# big_shield.net
KiCad netlist of a schematic drawn in EAGLE
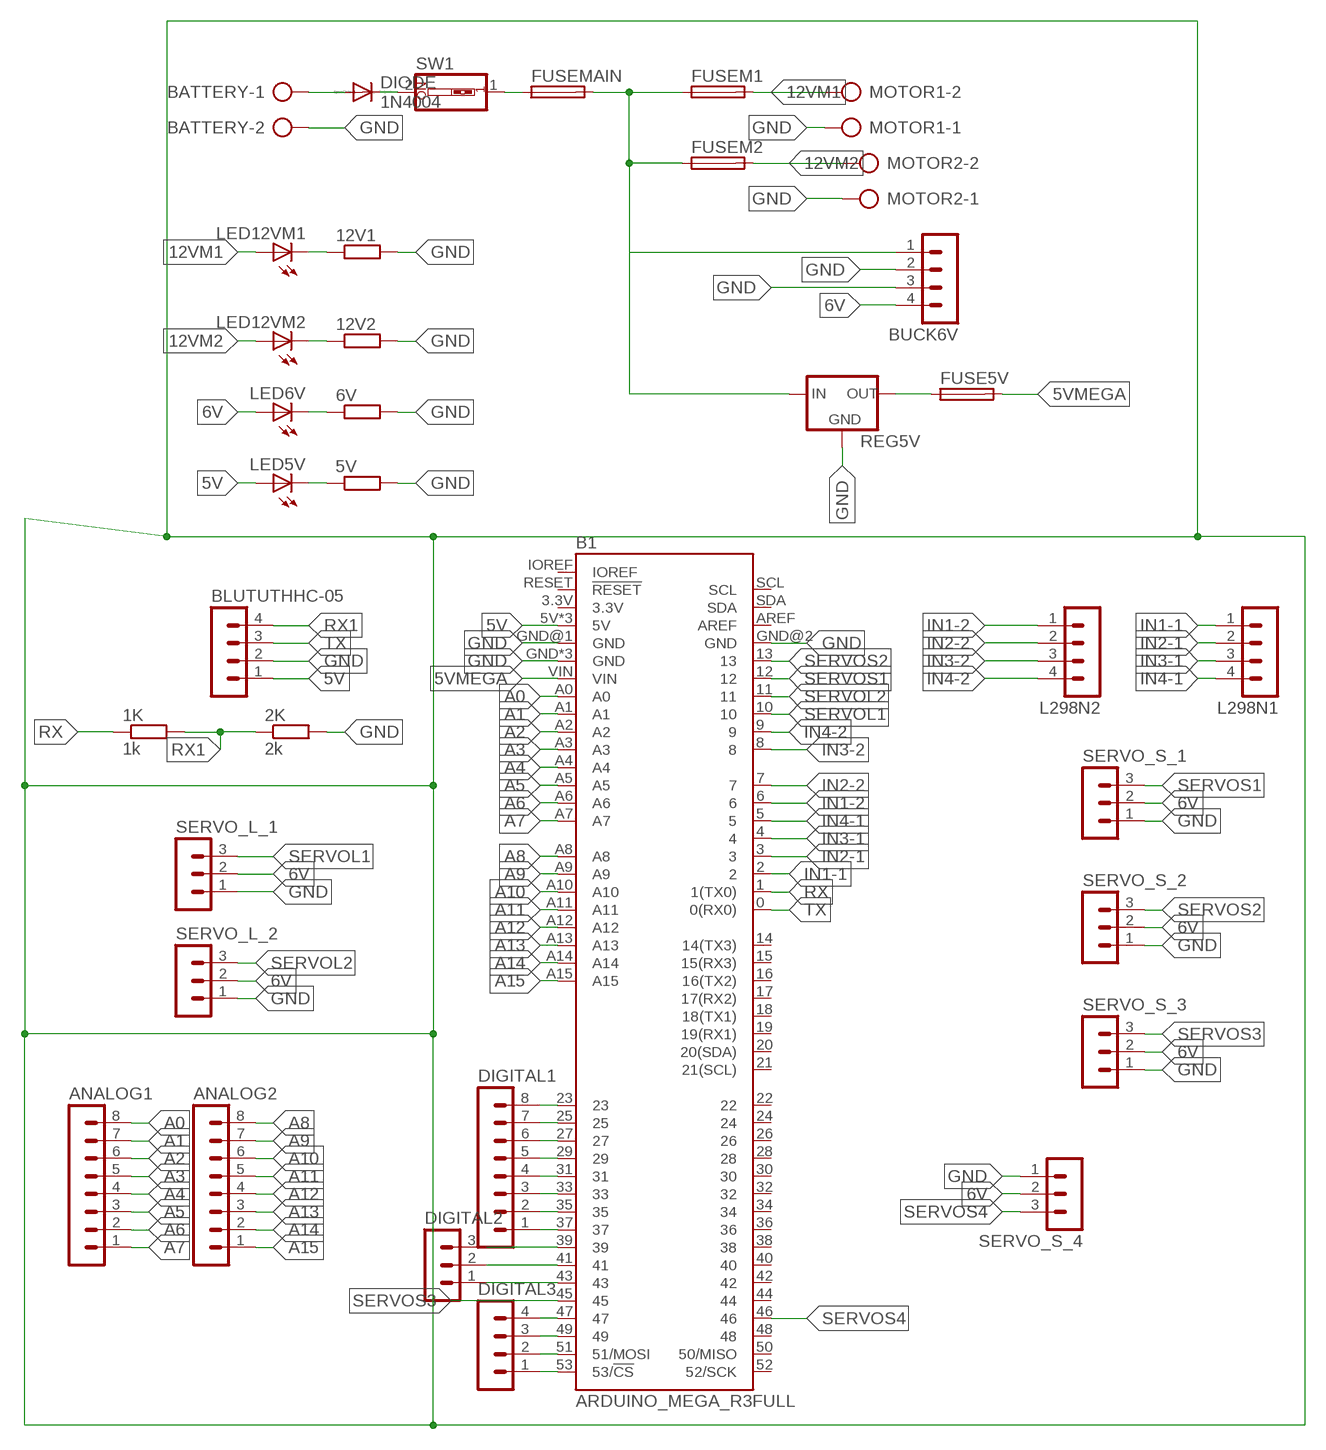
[diagram p0: schematic, sheet 1]

(export (version "E")
  (design (tool "Eeschema 10.0.6"))
  (components
    (comp (ref "1K")
      (value "1k")
      (footprint "eagle-import:0207_10")
      (libsource (lib "eagle-import") (part "R-EU_0207/10"))
    )
    (comp (ref "2K")
      (value "2k")
      (footprint "eagle-import:0207_10")
      (libsource (lib "eagle-import") (part "R-EU_0207/10"))
    )
    (comp (ref "5V")
      (value "R-EU_0204/7")
      (footprint "eagle-import:0204_7")
      (libsource (lib "eagle-import") (part "resistor_348_R-EU_0204/7"))
    )
    (comp (ref "6V")
      (value "R-EU_0204/7")
      (footprint "eagle-import:0204_7")
      (libsource (lib "eagle-import") (part "resistor_348_R-EU_0204/7"))
    )
    (comp (ref "12V1")
      (value "R-EU_0204/7")
      (footprint "eagle-import:0204_7")
      (libsource (lib "eagle-import") (part "resistor_348_R-EU_0204/7"))
    )
    (comp (ref "12V2")
      (value "R-EU_0204/7")
      (footprint "eagle-import:0204_7")
      (libsource (lib "eagle-import") (part "resistor_348_R-EU_0204/7"))
    )
    (comp (ref "ANALOG1")
      (value "MA08-1")
      (footprint "eagle-import:MA08-1")
      (libsource (lib "eagle-import") (part "MA08-1"))
    )
    (comp (ref "ANALOG2")
      (value "MA08-1")
      (footprint "eagle-import:MA08-1")
      (libsource (lib "eagle-import") (part "MA08-1"))
    )
    (comp (ref "B1")
      (value "ARDUINO_MEGA_R3FULL")
      (footprint "eagle-import:ARDUINO_MEGA_NO_SILK")
      (libsource (lib "eagle-import") (part "ARDUINO_MEGA_R3FULL"))
    )
    (comp (ref "BATTERY")
      (value "AK500/2-H")
      (footprint "eagle-import:AK500_2-H")
      (libsource (lib "eagle-import") (part "AK500/2-H"))
    )
    (comp (ref "BLUTUTHHC-05")
      (value "MA04-1")
      (footprint "eagle-import:MA04-1")
      (libsource (lib "eagle-import") (part "MA04-1"))
    )
    (comp (ref "BUCK6V")
      (value "MA04-1")
      (footprint "eagle-import:MA04-1")
      (libsource (lib "eagle-import") (part "MA04-1"))
    )
    (comp (ref "DIGITAL1")
      (value "MA08-1")
      (footprint "eagle-import:MA08-1")
      (libsource (lib "eagle-import") (part "MA08-1"))
    )
    (comp (ref "DIGITAL2")
      (value "MA03-1")
      (footprint "eagle-import:MA03-1")
      (libsource (lib "eagle-import") (part "MA03-1"))
    )
    (comp (ref "DIGITAL3")
      (value "MA04-1")
      (footprint "eagle-import:MA04-1")
      (libsource (lib "eagle-import") (part "MA04-1"))
    )
    (comp (ref "DIODE")
      (value "1N4004")
      (footprint "eagle-import:DO41-10")
      (libsource (lib "eagle-import") (part "1N4004"))
    )
    (comp (ref "FUSE5V")
      (value "SH22,5")
      (footprint "eagle-import:SH22,5")
      (fields (field (name "MF") "SCHURTER") (field (name "MPN") "0031.8201"))
      (libsource (lib "eagle-import") (part "SH22,5"))
    )
    (comp (ref "FUSEM1")
      (value "SH22,5")
      (footprint "eagle-import:SH22,5")
      (fields (field (name "MF") "SCHURTER") (field (name "MPN") "0031.8201"))
      (libsource (lib "eagle-import") (part "SH22,5"))
    )
    (comp (ref "FUSEM2")
      (value "SH22,5")
      (footprint "eagle-import:SH22,5")
      (fields (field (name "MF") "SCHURTER") (field (name "MPN") "0031.8201"))
      (libsource (lib "eagle-import") (part "SH22,5"))
    )
    (comp (ref "FUSEMAIN")
      (value "SH22,5")
      (footprint "eagle-import:SH22,5")
      (fields (field (name "MF") "SCHURTER") (field (name "MPN") "0031.8201"))
      (libsource (lib "eagle-import") (part "SH22,5"))
    )
    (comp (ref "L298N1")
      (value "MA04-1")
      (footprint "eagle-import:MA04-1")
      (libsource (lib "eagle-import") (part "MA04-1"))
    )
    (comp (ref "L298N2")
      (value "MA04-1")
      (footprint "eagle-import:MA04-1")
      (libsource (lib "eagle-import") (part "MA04-1"))
    )
    (comp (ref "LED5V")
      (value "LEDLSU260")
      (footprint "eagle-import:LSU260")
      (libsource (lib "eagle-import") (part "LEDLSU260"))
    )
    (comp (ref "LED6V")
      (value "LEDLSU260")
      (footprint "eagle-import:LSU260")
      (libsource (lib "eagle-import") (part "LEDLSU260"))
    )
    (comp (ref "LED12VM1")
      (value "LEDLSU260")
      (footprint "eagle-import:LSU260")
      (libsource (lib "eagle-import") (part "LEDLSU260"))
    )
    (comp (ref "LED12VM2")
      (value "LEDLSU260")
      (footprint "eagle-import:LSU260")
      (libsource (lib "eagle-import") (part "LEDLSU260"))
    )
    (comp (ref "MOTOR1")
      (value "AK500/2-H")
      (footprint "eagle-import:AK500_2-H")
      (libsource (lib "eagle-import") (part "AK500/2-H"))
    )
    (comp (ref "MOTOR2")
      (value "AK500/2-H")
      (footprint "eagle-import:AK500_2-H")
      (libsource (lib "eagle-import") (part "AK500/2-H"))
    )
    (comp (ref "REG5V")
      (value "78XXS")
      (footprint "eagle-import:78XXS")
      (libsource (lib "eagle-import") (part "78XXS"))
    )
    (comp (ref "SERVO_L_1")
      (value "MA03-1")
      (footprint "eagle-import:MA03-1")
      (libsource (lib "eagle-import") (part "MA03-1"))
    )
    (comp (ref "SERVO_L_2")
      (value "MA03-1")
      (footprint "eagle-import:MA03-1")
      (libsource (lib "eagle-import") (part "MA03-1"))
    )
    (comp (ref "SERVO_S_1")
      (value "MA03-1")
      (footprint "eagle-import:MA03-1")
      (libsource (lib "eagle-import") (part "MA03-1"))
    )
    (comp (ref "SERVO_S_2")
      (value "MA03-1")
      (footprint "eagle-import:MA03-1")
      (libsource (lib "eagle-import") (part "MA03-1"))
    )
    (comp (ref "SERVO_S_3")
      (value "MA03-1")
      (footprint "eagle-import:MA03-1")
      (libsource (lib "eagle-import") (part "MA03-1"))
    )
    (comp (ref "SERVO_S_4")
      (value "MA03-1")
      (footprint "eagle-import:MA03-1")
      (libsource (lib "eagle-import") (part "MA03-1"))
    )
    (comp (ref "SW1")
      (value "SW_DIP-1")
      (footprint "eagle-import:EDG-01")
      (libsource (lib "eagle-import") (part "SW_DIP-1"))
    )
  )
  (nets
    (net (code "1") (name "5V") (class "Default")
      (node (ref "B1") (pin "5V") (pinfunction "5V_5V") (pintype "bidirectional"))
      (node (ref "B1") (pin "5V@1") (pinfunction "5V_5V@1") (pintype "bidirectional"))
      (node (ref "B1") (pin "5V@2") (pinfunction "5V_5V@2") (pintype "bidirectional"))
      (node (ref "BLUTUTHHC-05") (pin "1") (pinfunction "1_1") (pintype "passive"))
      (node (ref "LED5V") (pin "A") (pinfunction "A_A") (pintype "passive"))
    )
    (net (code "2") (name "5VMEGA") (class "Default")
      (node (ref "B1") (pin "VIN") (pinfunction "VIN_VIN") (pintype "bidirectional"))
      (node (ref "FUSE5V") (pin "2") (pinfunction "2_2") (pintype "passive"))
    )
    (net (code "3") (name "6V") (class "Default")
      (node (ref "BUCK6V") (pin "4") (pinfunction "4_4") (pintype "passive"))
      (node (ref "LED6V") (pin "A") (pinfunction "A_A") (pintype "passive"))
      (node (ref "SERVO_L_1") (pin "2") (pinfunction "2_2") (pintype "passive"))
      (node (ref "SERVO_L_2") (pin "2") (pinfunction "2_2") (pintype "passive"))
      (node (ref "SERVO_S_1") (pin "2") (pinfunction "2_2") (pintype "passive"))
      (node (ref "SERVO_S_2") (pin "2") (pinfunction "2_2") (pintype "passive"))
      (node (ref "SERVO_S_3") (pin "2") (pinfunction "2_2") (pintype "passive"))
      (node (ref "SERVO_S_4") (pin "2") (pinfunction "2_2") (pintype "passive"))
    )
    (net (code "4") (name "12VM1") (class "Default")
      (node (ref "FUSEM1") (pin "2") (pinfunction "2_2") (pintype "passive"))
      (node (ref "LED12VM1") (pin "A") (pinfunction "A_A") (pintype "passive"))
      (node (ref "MOTOR1") (pin "2") (pinfunction "KL_2") (pintype "passive"))
    )
    (net (code "5") (name "12VM2") (class "Default")
      (node (ref "FUSEM2") (pin "2") (pinfunction "2_2") (pintype "passive"))
      (node (ref "LED12VM2") (pin "A") (pinfunction "A_A") (pintype "passive"))
      (node (ref "MOTOR2") (pin "2") (pinfunction "KL_2") (pintype "passive"))
    )
    (net (code "6") (name "A0") (class "Default")
      (node (ref "ANALOG1") (pin "8") (pinfunction "8_8") (pintype "passive"))
      (node (ref "B1") (pin "A0") (pinfunction "A0_A0") (pintype "bidirectional"))
    )
    (net (code "7") (name "A1") (class "Default")
      (node (ref "ANALOG1") (pin "7") (pinfunction "7_7") (pintype "passive"))
      (node (ref "B1") (pin "A1") (pinfunction "A1_A1") (pintype "bidirectional"))
    )
    (net (code "8") (name "A2") (class "Default")
      (node (ref "ANALOG1") (pin "6") (pinfunction "6_6") (pintype "passive"))
      (node (ref "B1") (pin "A2") (pinfunction "A2_A2") (pintype "bidirectional"))
    )
    (net (code "9") (name "A3") (class "Default")
      (node (ref "ANALOG1") (pin "5") (pinfunction "5_5") (pintype "passive"))
      (node (ref "B1") (pin "A3") (pinfunction "A3_A3") (pintype "bidirectional"))
    )
    (net (code "10") (name "A4") (class "Default")
      (node (ref "ANALOG1") (pin "4") (pinfunction "4_4") (pintype "passive"))
      (node (ref "B1") (pin "A4") (pinfunction "A4_A4") (pintype "bidirectional"))
    )
    (net (code "11") (name "A5") (class "Default")
      (node (ref "ANALOG1") (pin "3") (pinfunction "3_3") (pintype "passive"))
      (node (ref "B1") (pin "A5") (pinfunction "A5_A5") (pintype "bidirectional"))
    )
    (net (code "12") (name "A6") (class "Default")
      (node (ref "ANALOG1") (pin "2") (pinfunction "2_2") (pintype "passive"))
      (node (ref "B1") (pin "A6") (pinfunction "A6_A6") (pintype "bidirectional"))
    )
    (net (code "13") (name "A7") (class "Default")
      (node (ref "ANALOG1") (pin "1") (pinfunction "1_1") (pintype "passive"))
      (node (ref "B1") (pin "A7") (pinfunction "A7_A7") (pintype "bidirectional"))
    )
    (net (code "14") (name "A8") (class "Default")
      (node (ref "ANALOG2") (pin "8") (pinfunction "8_8") (pintype "passive"))
      (node (ref "B1") (pin "A8") (pinfunction "A8_A8") (pintype "bidirectional"))
    )
    (net (code "15") (name "A9") (class "Default")
      (node (ref "ANALOG2") (pin "7") (pinfunction "7_7") (pintype "passive"))
      (node (ref "B1") (pin "A9") (pinfunction "A9_A9") (pintype "bidirectional"))
    )
    (net (code "16") (name "A10") (class "Default")
      (node (ref "ANALOG2") (pin "6") (pinfunction "6_6") (pintype "passive"))
      (node (ref "B1") (pin "A10") (pinfunction "A10_A10") (pintype "bidirectional"))
    )
    (net (code "17") (name "A11") (class "Default")
      (node (ref "ANALOG2") (pin "5") (pinfunction "5_5") (pintype "passive"))
      (node (ref "B1") (pin "A11") (pinfunction "A11_A11") (pintype "bidirectional"))
    )
    (net (code "18") (name "A12") (class "Default")
      (node (ref "ANALOG2") (pin "4") (pinfunction "4_4") (pintype "passive"))
      (node (ref "B1") (pin "A12") (pinfunction "A12_A12") (pintype "bidirectional"))
    )
    (net (code "19") (name "A13") (class "Default")
      (node (ref "ANALOG2") (pin "3") (pinfunction "3_3") (pintype "passive"))
      (node (ref "B1") (pin "A13") (pinfunction "A13_A13") (pintype "bidirectional"))
    )
    (net (code "20") (name "A14") (class "Default")
      (node (ref "ANALOG2") (pin "2") (pinfunction "2_2") (pintype "passive"))
      (node (ref "B1") (pin "A14") (pinfunction "A14_A14") (pintype "bidirectional"))
    )
    (net (code "21") (name "A15") (class "Default")
      (node (ref "ANALOG2") (pin "1") (pinfunction "1_1") (pintype "passive"))
      (node (ref "B1") (pin "A15") (pinfunction "A15_A15") (pintype "bidirectional"))
    )
    (net (code "22") (name "GND") (class "Default")
      (node (ref "12V1") (pin "2") (pinfunction "2_2") (pintype "passive"))
      (node (ref "12V2") (pin "2") (pinfunction "2_2") (pintype "passive"))
      (node (ref "2K") (pin "2") (pinfunction "2_2") (pintype "passive"))
      (node (ref "5V") (pin "2") (pinfunction "2_2") (pintype "passive"))
      (node (ref "6V") (pin "2") (pinfunction "2_2") (pintype "passive"))
      (node (ref "B1") (pin "GND") (pinfunction "GND_GND") (pintype "bidirectional"))
      (node (ref "B1") (pin "GND@1") (pinfunction "GND_GND@1") (pintype "bidirectional"))
      (node (ref "B1") (pin "GND@2") (pinfunction "GND_GND@2") (pintype "bidirectional"))
      (node (ref "B1") (pin "GND@3") (pinfunction "GND_GND@3") (pintype "bidirectional"))
      (node (ref "B1") (pin "GND@4") (pinfunction "GND_GND@4") (pintype "bidirectional"))
      (node (ref "BATTERY") (pin "2") (pinfunction "KL_2") (pintype "passive"))
      (node (ref "BLUTUTHHC-05") (pin "2") (pinfunction "2_2") (pintype "passive"))
      (node (ref "BUCK6V") (pin "2") (pinfunction "2_2") (pintype "passive"))
      (node (ref "BUCK6V") (pin "3") (pinfunction "3_3") (pintype "passive"))
      (node (ref "MOTOR1") (pin "1") (pinfunction "KL_1") (pintype "passive"))
      (node (ref "MOTOR2") (pin "1") (pinfunction "KL_1") (pintype "passive"))
      (node (ref "REG5V") (pin "GND") (pinfunction "GND_GND") (pintype "input"))
      (node (ref "SERVO_L_1") (pin "1") (pinfunction "1_1") (pintype "passive"))
      (node (ref "SERVO_L_2") (pin "1") (pinfunction "1_1") (pintype "passive"))
      (node (ref "SERVO_S_1") (pin "1") (pinfunction "1_1") (pintype "passive"))
      (node (ref "SERVO_S_2") (pin "1") (pinfunction "1_1") (pintype "passive"))
      (node (ref "SERVO_S_3") (pin "1") (pinfunction "1_1") (pintype "passive"))
      (node (ref "SERVO_S_4") (pin "1") (pinfunction "1_1") (pintype "passive"))
    )
    (net (code "23") (name "IN1-1") (class "Default")
      (node (ref "B1") (pin "2") (pinfunction "2_2") (pintype "bidirectional"))
      (node (ref "L298N1") (pin "1") (pinfunction "1_1") (pintype "passive"))
    )
    (net (code "24") (name "IN1-2") (class "Default")
      (node (ref "B1") (pin "6") (pinfunction "6_6") (pintype "bidirectional"))
      (node (ref "L298N2") (pin "1") (pinfunction "1_1") (pintype "passive"))
    )
    (net (code "25") (name "IN2-1") (class "Default")
      (node (ref "B1") (pin "3") (pinfunction "3_3") (pintype "bidirectional"))
      (node (ref "L298N1") (pin "2") (pinfunction "2_2") (pintype "passive"))
    )
    (net (code "26") (name "IN2-2") (class "Default")
      (node (ref "B1") (pin "7") (pinfunction "7_7") (pintype "bidirectional"))
      (node (ref "L298N2") (pin "2") (pinfunction "2_2") (pintype "passive"))
    )
    (net (code "27") (name "IN3-1") (class "Default")
      (node (ref "B1") (pin "4") (pinfunction "4_4") (pintype "bidirectional"))
      (node (ref "L298N1") (pin "3") (pinfunction "3_3") (pintype "passive"))
    )
    (net (code "28") (name "IN3-2") (class "Default")
      (node (ref "B1") (pin "8") (pinfunction "8_8") (pintype "bidirectional"))
      (node (ref "L298N2") (pin "3") (pinfunction "3_3") (pintype "passive"))
    )
    (net (code "29") (name "IN4-1") (class "Default")
      (node (ref "B1") (pin "5") (pinfunction "5_5") (pintype "bidirectional"))
      (node (ref "L298N1") (pin "4") (pinfunction "4_4") (pintype "passive"))
    )
    (net (code "30") (name "IN4-2") (class "Default")
      (node (ref "B1") (pin "9") (pinfunction "9_9") (pintype "bidirectional"))
      (node (ref "L298N2") (pin "4") (pinfunction "4_4") (pintype "passive"))
    )
    (net (code "31") (name "Net-(B1-51{slash}MOSI)") (class "Default")
      (node (ref "B1") (pin "51") (pinfunction "51/MOSI_51") (pintype "bidirectional"))
      (node (ref "DIGITAL3") (pin "2") (pinfunction "2_2") (pintype "passive"))
    )
    (net (code "32") (name "Net-(B1-53{slash}~{CS})") (class "Default")
      (node (ref "B1") (pin "53") (pinfunction "53/~{CS}_53") (pintype "bidirectional"))
      (node (ref "DIGITAL3") (pin "1") (pinfunction "1_1") (pintype "passive"))
    )
    (net (code "33") (name "Net-(B1-Pad23)") (class "Default")
      (node (ref "B1") (pin "23") (pinfunction "23_23") (pintype "bidirectional"))
      (node (ref "DIGITAL1") (pin "8") (pinfunction "8_8") (pintype "passive"))
    )
    (net (code "34") (name "Net-(B1-Pad25)") (class "Default")
      (node (ref "B1") (pin "25") (pinfunction "25_25") (pintype "bidirectional"))
      (node (ref "DIGITAL1") (pin "7") (pinfunction "7_7") (pintype "passive"))
    )
    (net (code "35") (name "Net-(B1-Pad27)") (class "Default")
      (node (ref "B1") (pin "27") (pinfunction "27_27") (pintype "bidirectional"))
      (node (ref "DIGITAL1") (pin "6") (pinfunction "6_6") (pintype "passive"))
    )
    (net (code "36") (name "Net-(B1-Pad29)") (class "Default")
      (node (ref "B1") (pin "29") (pinfunction "29_29") (pintype "bidirectional"))
      (node (ref "DIGITAL1") (pin "5") (pinfunction "5_5") (pintype "passive"))
    )
    (net (code "37") (name "Net-(B1-Pad31)") (class "Default")
      (node (ref "B1") (pin "31") (pinfunction "31_31") (pintype "bidirectional"))
      (node (ref "DIGITAL1") (pin "4") (pinfunction "4_4") (pintype "passive"))
    )
    (net (code "38") (name "Net-(B1-Pad33)") (class "Default")
      (node (ref "B1") (pin "33") (pinfunction "33_33") (pintype "bidirectional"))
      (node (ref "DIGITAL1") (pin "3") (pinfunction "3_3") (pintype "passive"))
    )
    (net (code "39") (name "Net-(B1-Pad35)") (class "Default")
      (node (ref "B1") (pin "35") (pinfunction "35_35") (pintype "bidirectional"))
      (node (ref "DIGITAL1") (pin "2") (pinfunction "2_2") (pintype "passive"))
    )
    (net (code "40") (name "Net-(B1-Pad37)") (class "Default")
      (node (ref "B1") (pin "37") (pinfunction "37_37") (pintype "bidirectional"))
      (node (ref "DIGITAL1") (pin "1") (pinfunction "1_1") (pintype "passive"))
    )
    (net (code "41") (name "Net-(B1-Pad39)") (class "Default")
      (node (ref "B1") (pin "39") (pinfunction "39_39") (pintype "bidirectional"))
      (node (ref "DIGITAL2") (pin "3") (pinfunction "3_3") (pintype "passive"))
    )
    (net (code "42") (name "Net-(B1-Pad41)") (class "Default")
      (node (ref "B1") (pin "41") (pinfunction "41_41") (pintype "bidirectional"))
      (node (ref "DIGITAL2") (pin "2") (pinfunction "2_2") (pintype "passive"))
    )
    (net (code "43") (name "Net-(B1-Pad43)") (class "Default")
      (node (ref "B1") (pin "43") (pinfunction "43_43") (pintype "bidirectional"))
      (node (ref "DIGITAL2") (pin "1") (pinfunction "1_1") (pintype "passive"))
    )
    (net (code "44") (name "Net-(B1-Pad47)") (class "Default")
      (node (ref "B1") (pin "47") (pinfunction "47_47") (pintype "bidirectional"))
      (node (ref "DIGITAL3") (pin "4") (pinfunction "4_4") (pintype "passive"))
    )
    (net (code "45") (name "Net-(B1-Pad49)") (class "Default")
      (node (ref "B1") (pin "49") (pinfunction "49_49") (pintype "bidirectional"))
      (node (ref "DIGITAL3") (pin "3") (pinfunction "3_3") (pintype "passive"))
    )
    (net (code "46") (name "Net-(BATTERYA-KL)") (class "Default")
      (node (ref "BATTERY") (pin "1") (pinfunction "KL_1") (pintype "passive"))
      (node (ref "DIODE") (pin "A") (pinfunction "A_A") (pintype "passive"))
    )
    (net (code "47") (name "Net-(BUCK6V-Pad1)") (class "Default")
      (node (ref "BUCK6V") (pin "1") (pinfunction "1_1") (pintype "passive"))
      (node (ref "FUSEM1") (pin "1") (pinfunction "1_1") (pintype "passive"))
      (node (ref "FUSEM2") (pin "1") (pinfunction "1_1") (pintype "passive"))
      (node (ref "FUSEMAIN") (pin "2") (pinfunction "2_2") (pintype "passive"))
      (node (ref "REG5V") (pin "IN") (pinfunction "IN_IN") (pintype "input"))
    )
    (net (code "48") (name "Net-(DIODE-PadC)") (class "Default")
      (node (ref "DIODE") (pin "C") (pinfunction "C_C") (pintype "passive"))
      (node (ref "SW1") (pin "2") (pinfunction "2_2") (pintype "passive"))
    )
    (net (code "49") (name "Net-(FUSE5V-Pad1)") (class "Default")
      (node (ref "FUSE5V") (pin "1") (pinfunction "1_1") (pintype "passive"))
      (node (ref "REG5V") (pin "OUT") (pinfunction "OUT_OUT") (pintype "passive"))
    )
    (net (code "50") (name "Net-(FUSEMAIN-Pad1)") (class "Default")
      (node (ref "FUSEMAIN") (pin "1") (pinfunction "1_1") (pintype "passive"))
      (node (ref "SW1") (pin "1") (pinfunction "1_1") (pintype "passive"))
    )
    (net (code "51") (name "Net-(LED5V-C)") (class "Default")
      (node (ref "5V") (pin "1") (pinfunction "1_1") (pintype "passive"))
      (node (ref "LED5V") (pin "K") (pinfunction "C_K") (pintype "passive"))
    )
    (net (code "52") (name "Net-(LED6V-C)") (class "Default")
      (node (ref "6V") (pin "1") (pinfunction "1_1") (pintype "passive"))
      (node (ref "LED6V") (pin "K") (pinfunction "C_K") (pintype "passive"))
    )
    (net (code "53") (name "Net-(LED12VM1-C)") (class "Default")
      (node (ref "12V1") (pin "1") (pinfunction "1_1") (pintype "passive"))
      (node (ref "LED12VM1") (pin "K") (pinfunction "C_K") (pintype "passive"))
    )
    (net (code "54") (name "Net-(LED12VM2-C)") (class "Default")
      (node (ref "12V2") (pin "1") (pinfunction "1_1") (pintype "passive"))
      (node (ref "LED12VM2") (pin "K") (pinfunction "C_K") (pintype "passive"))
    )
    (net (code "55") (name "RX") (class "Default")
      (node (ref "1K") (pin "1") (pinfunction "1_1") (pintype "passive"))
      (node (ref "B1") (pin "1") (pinfunction "1(TX0)_1") (pintype "bidirectional"))
    )
    (net (code "56") (name "RX1") (class "Default")
      (node (ref "1K") (pin "2") (pinfunction "2_2") (pintype "passive"))
      (node (ref "2K") (pin "1") (pinfunction "1_1") (pintype "passive"))
      (node (ref "BLUTUTHHC-05") (pin "4") (pinfunction "4_4") (pintype "passive"))
    )
    (net (code "57") (name "SERVOL1") (class "Default")
      (node (ref "B1") (pin "10") (pinfunction "10_10") (pintype "bidirectional"))
      (node (ref "SERVO_L_1") (pin "3") (pinfunction "3_3") (pintype "passive"))
    )
    (net (code "58") (name "SERVOL2") (class "Default")
      (node (ref "B1") (pin "11") (pinfunction "11_11") (pintype "bidirectional"))
      (node (ref "SERVO_L_2") (pin "3") (pinfunction "3_3") (pintype "passive"))
    )
    (net (code "59") (name "SERVOS1") (class "Default")
      (node (ref "B1") (pin "12") (pinfunction "12_12") (pintype "bidirectional"))
      (node (ref "SERVO_S_1") (pin "3") (pinfunction "3_3") (pintype "passive"))
    )
    (net (code "60") (name "SERVOS2") (class "Default")
      (node (ref "B1") (pin "13") (pinfunction "13_13") (pintype "bidirectional"))
      (node (ref "SERVO_S_2") (pin "3") (pinfunction "3_3") (pintype "passive"))
    )
    (net (code "61") (name "SERVOS3") (class "Default")
      (node (ref "B1") (pin "45") (pinfunction "45_45") (pintype "bidirectional"))
      (node (ref "SERVO_S_3") (pin "3") (pinfunction "3_3") (pintype "passive"))
    )
    (net (code "62") (name "SERVOS4") (class "Default")
      (node (ref "B1") (pin "46") (pinfunction "46_46") (pintype "bidirectional"))
      (node (ref "SERVO_S_4") (pin "3") (pinfunction "3_3") (pintype "passive"))
    )
    (net (code "63") (name "TX") (class "Default")
      (node (ref "B1") (pin "0") (pinfunction "0(RX0)_0") (pintype "bidirectional"))
      (node (ref "BLUTUTHHC-05") (pin "3") (pinfunction "3_3") (pintype "passive"))
    )
    (net (code "64") (name "unconnected-(B1-14(TX3)-Pad14)") (class "Default")
      (node (ref "B1") (pin "14") (pinfunction "14(TX3)_14") (pintype "bidirectional"))
    )
    (net (code "65") (name "unconnected-(B1-15(RX3)-Pad15)") (class "Default")
      (node (ref "B1") (pin "15") (pinfunction "15(RX3)_15") (pintype "bidirectional"))
    )
    (net (code "66") (name "unconnected-(B1-16(TX2)-Pad16)") (class "Default")
      (node (ref "B1") (pin "16") (pinfunction "16(TX2)_16") (pintype "bidirectional"))
    )
    (net (code "67") (name "unconnected-(B1-17(RX2)-Pad17)") (class "Default")
      (node (ref "B1") (pin "17") (pinfunction "17(RX2)_17") (pintype "bidirectional"))
    )
    (net (code "68") (name "unconnected-(B1-18(TX1)-Pad18)") (class "Default")
      (node (ref "B1") (pin "18") (pinfunction "18(TX1)_18") (pintype "bidirectional"))
    )
    (net (code "69") (name "unconnected-(B1-19(RX1)-Pad19)") (class "Default")
      (node (ref "B1") (pin "19") (pinfunction "19(RX1)_19") (pintype "bidirectional"))
    )
    (net (code "70") (name "unconnected-(B1-20(SDA)-Pad20)") (class "Default")
      (node (ref "B1") (pin "20") (pinfunction "20(SDA)_20") (pintype "bidirectional"))
    )
    (net (code "71") (name "unconnected-(B1-21(SCL)-Pad21)") (class "Default")
      (node (ref "B1") (pin "21") (pinfunction "21(SCL)_21") (pintype "bidirectional"))
    )
    (net (code "72") (name "unconnected-(B1-50{slash}MISO-Pad50)") (class "Default")
      (node (ref "B1") (pin "50") (pinfunction "50/MISO_50") (pintype "bidirectional"))
    )
    (net (code "73") (name "unconnected-(B1-52{slash}SCK-Pad52)") (class "Default")
      (node (ref "B1") (pin "52") (pinfunction "52/SCK_52") (pintype "bidirectional"))
    )
    (net (code "74") (name "unconnected-(B1-Pad3.3V)") (class "Default")
      (node (ref "B1") (pin "3.3V") (pinfunction "3.3V_3.3V") (pintype "bidirectional"))
    )
    (net (code "75") (name "unconnected-(B1-Pad22)") (class "Default")
      (node (ref "B1") (pin "22") (pinfunction "22_22") (pintype "bidirectional"))
    )
    (net (code "76") (name "unconnected-(B1-Pad24)") (class "Default")
      (node (ref "B1") (pin "24") (pinfunction "24_24") (pintype "bidirectional"))
    )
    (net (code "77") (name "unconnected-(B1-Pad26)") (class "Default")
      (node (ref "B1") (pin "26") (pinfunction "26_26") (pintype "bidirectional"))
    )
    (net (code "78") (name "unconnected-(B1-Pad28)") (class "Default")
      (node (ref "B1") (pin "28") (pinfunction "28_28") (pintype "bidirectional"))
    )
    (net (code "79") (name "unconnected-(B1-Pad30)") (class "Default")
      (node (ref "B1") (pin "30") (pinfunction "30_30") (pintype "bidirectional"))
    )
    (net (code "80") (name "unconnected-(B1-Pad32)") (class "Default")
      (node (ref "B1") (pin "32") (pinfunction "32_32") (pintype "bidirectional"))
    )
    (net (code "81") (name "unconnected-(B1-Pad34)") (class "Default")
      (node (ref "B1") (pin "34") (pinfunction "34_34") (pintype "bidirectional"))
    )
    (net (code "82") (name "unconnected-(B1-Pad36)") (class "Default")
      (node (ref "B1") (pin "36") (pinfunction "36_36") (pintype "bidirectional"))
    )
    (net (code "83") (name "unconnected-(B1-Pad38)") (class "Default")
      (node (ref "B1") (pin "38") (pinfunction "38_38") (pintype "bidirectional"))
    )
    (net (code "84") (name "unconnected-(B1-Pad40)") (class "Default")
      (node (ref "B1") (pin "40") (pinfunction "40_40") (pintype "bidirectional"))
    )
    (net (code "85") (name "unconnected-(B1-Pad42)") (class "Default")
      (node (ref "B1") (pin "42") (pinfunction "42_42") (pintype "bidirectional"))
    )
    (net (code "86") (name "unconnected-(B1-Pad44)") (class "Default")
      (node (ref "B1") (pin "44") (pinfunction "44_44") (pintype "bidirectional"))
    )
    (net (code "87") (name "unconnected-(B1-Pad48)") (class "Default")
      (node (ref "B1") (pin "48") (pinfunction "48_48") (pintype "bidirectional"))
    )
    (net (code "88") (name "unconnected-(B1-PadAREF)") (class "Default")
      (node (ref "B1") (pin "AREF") (pinfunction "AREF_AREF") (pintype "bidirectional"))
    )
    (net (code "89") (name "unconnected-(B1-PadIOREF)") (class "Default")
      (node (ref "B1") (pin "IOREF") (pinfunction "IOREF_IOREF") (pintype "bidirectional"))
    )
    (net (code "90") (name "unconnected-(B1-PadSCL)") (class "Default")
      (node (ref "B1") (pin "SCL") (pinfunction "SCL_SCL") (pintype "bidirectional"))
    )
    (net (code "91") (name "unconnected-(B1-PadSDA)") (class "Default")
      (node (ref "B1") (pin "SDA") (pinfunction "SDA_SDA") (pintype "bidirectional"))
    )
    (net (code "92") (name "unconnected-(B1-~{RESET}-PadRESET)") (class "Default")
      (node (ref "B1") (pin "RESET") (pinfunction "~{RESET}_RESET") (pintype "bidirectional"))
    )
  )
)
